# sheet1.net
KiCad netlist of a schematic drawn in Altium Designer
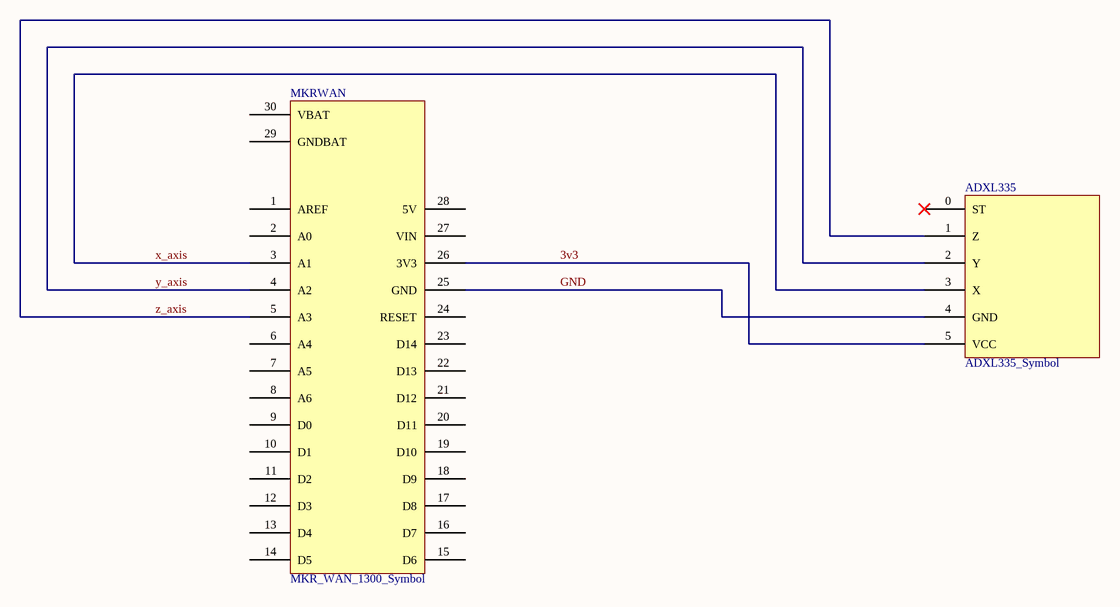
[diagram p0: sheet1.SchDoc]

(export (version "E")
  (design (tool "Eeschema 10.0.6"))
  (components
    (comp (ref "ADXL335")
      (value "ADXL335_Symbol")
      (footprint "ADXL335_HEADERS")
      (libsource (lib "Schlib1") (part "ADXL335_Symbol"))
    )
    (comp (ref "MKRWAN")
      (value "MKR_WAN_1300_Symbol")
      (footprint "MKR_WAN_1300_Headers")
      (libsource (lib "Schlib1") (part "MKR_WAN_1300_Symbol"))
    )
  )
  (nets
    (net (code "1") (name "/3v3") (class "Default")
      (node (ref "ADXL335") (pin "5") (pinfunction "VCC_5") (pintype "passive"))
      (node (ref "MKRWAN") (pin "26") (pinfunction "3V3_26") (pintype "passive"))
    )
    (net (code "2") (name "/GND") (class "Default")
      (node (ref "ADXL335") (pin "4") (pinfunction "GND_4") (pintype "passive"))
      (node (ref "MKRWAN") (pin "25") (pinfunction "GND_25") (pintype "passive"))
    )
    (net (code "3") (name "/x_axis") (class "Default")
      (node (ref "ADXL335") (pin "3") (pinfunction "X_3") (pintype "passive"))
      (node (ref "MKRWAN") (pin "3") (pinfunction "A1_3") (pintype "passive"))
    )
    (net (code "4") (name "/y_axis") (class "Default")
      (node (ref "ADXL335") (pin "2") (pinfunction "Y_2") (pintype "passive"))
      (node (ref "MKRWAN") (pin "4") (pinfunction "A2_4") (pintype "passive"))
    )
    (net (code "5") (name "/z_axis") (class "Default")
      (node (ref "ADXL335") (pin "1") (pinfunction "Z_1") (pintype "passive"))
      (node (ref "MKRWAN") (pin "5") (pinfunction "A3_5") (pintype "passive"))
    )
    (net (code "6") (name "unconnected-(ADXL335-ST-Pad0)") (class "Default")
      (node (ref "ADXL335") (pin "0") (pinfunction "ST_0") (pintype "passive+no_connect"))
    )
    (net (code "7") (name "unconnected-(MKRWAN-5V-Pad28)") (class "Default")
      (node (ref "MKRWAN") (pin "28") (pinfunction "5V_28") (pintype "passive"))
    )
    (net (code "8") (name "unconnected-(MKRWAN-A0-Pad2)") (class "Default")
      (node (ref "MKRWAN") (pin "2") (pinfunction "A0_2") (pintype "passive"))
    )
    (net (code "9") (name "unconnected-(MKRWAN-A4-Pad6)") (class "Default")
      (node (ref "MKRWAN") (pin "6") (pinfunction "A4_6") (pintype "passive"))
    )
    (net (code "10") (name "unconnected-(MKRWAN-A5-Pad7)") (class "Default")
      (node (ref "MKRWAN") (pin "7") (pinfunction "A5_7") (pintype "passive"))
    )
    (net (code "11") (name "unconnected-(MKRWAN-A6-Pad8)") (class "Default")
      (node (ref "MKRWAN") (pin "8") (pinfunction "A6_8") (pintype "passive"))
    )
    (net (code "12") (name "unconnected-(MKRWAN-AREF-Pad1)") (class "Default")
      (node (ref "MKRWAN") (pin "1") (pinfunction "AREF_1") (pintype "passive"))
    )
    (net (code "13") (name "unconnected-(MKRWAN-D0-Pad9)") (class "Default")
      (node (ref "MKRWAN") (pin "9") (pinfunction "D0_9") (pintype "passive"))
    )
    (net (code "14") (name "unconnected-(MKRWAN-D1-Pad10)") (class "Default")
      (node (ref "MKRWAN") (pin "10") (pinfunction "D1_10") (pintype "passive"))
    )
    (net (code "15") (name "unconnected-(MKRWAN-D2-Pad11)") (class "Default")
      (node (ref "MKRWAN") (pin "11") (pinfunction "D2_11") (pintype "passive"))
    )
    (net (code "16") (name "unconnected-(MKRWAN-D3-Pad12)") (class "Default")
      (node (ref "MKRWAN") (pin "12") (pinfunction "D3_12") (pintype "passive"))
    )
    (net (code "17") (name "unconnected-(MKRWAN-D4-Pad13)") (class "Default")
      (node (ref "MKRWAN") (pin "13") (pinfunction "D4_13") (pintype "passive"))
    )
    (net (code "18") (name "unconnected-(MKRWAN-D5-Pad14)") (class "Default")
      (node (ref "MKRWAN") (pin "14") (pinfunction "D5_14") (pintype "passive"))
    )
    (net (code "19") (name "unconnected-(MKRWAN-D6-Pad15)") (class "Default")
      (node (ref "MKRWAN") (pin "15") (pinfunction "D6_15") (pintype "passive"))
    )
    (net (code "20") (name "unconnected-(MKRWAN-D7-Pad16)") (class "Default")
      (node (ref "MKRWAN") (pin "16") (pinfunction "D7_16") (pintype "passive"))
    )
    (net (code "21") (name "unconnected-(MKRWAN-D8-Pad17)") (class "Default")
      (node (ref "MKRWAN") (pin "17") (pinfunction "D8_17") (pintype "passive"))
    )
    (net (code "22") (name "unconnected-(MKRWAN-D9-Pad18)") (class "Default")
      (node (ref "MKRWAN") (pin "18") (pinfunction "D9_18") (pintype "passive"))
    )
    (net (code "23") (name "unconnected-(MKRWAN-D10-Pad19)") (class "Default")
      (node (ref "MKRWAN") (pin "19") (pinfunction "D10_19") (pintype "passive"))
    )
    (net (code "24") (name "unconnected-(MKRWAN-D11-Pad20)") (class "Default")
      (node (ref "MKRWAN") (pin "20") (pinfunction "D11_20") (pintype "passive"))
    )
    (net (code "25") (name "unconnected-(MKRWAN-D12-Pad21)") (class "Default")
      (node (ref "MKRWAN") (pin "21") (pinfunction "D12_21") (pintype "passive"))
    )
    (net (code "26") (name "unconnected-(MKRWAN-D13-Pad22)") (class "Default")
      (node (ref "MKRWAN") (pin "22") (pinfunction "D13_22") (pintype "passive"))
    )
    (net (code "27") (name "unconnected-(MKRWAN-D14-Pad23)") (class "Default")
      (node (ref "MKRWAN") (pin "23") (pinfunction "D14_23") (pintype "passive"))
    )
    (net (code "28") (name "unconnected-(MKRWAN-GNDBAT-Pad29)") (class "Default")
      (node (ref "MKRWAN") (pin "29") (pinfunction "GNDBAT_29") (pintype "passive"))
    )
    (net (code "29") (name "unconnected-(MKRWAN-RESET-Pad24)") (class "Default")
      (node (ref "MKRWAN") (pin "24") (pinfunction "RESET_24") (pintype "passive"))
    )
    (net (code "30") (name "unconnected-(MKRWAN-VBAT-Pad30)") (class "Default")
      (node (ref "MKRWAN") (pin "30") (pinfunction "VBAT_30") (pintype "passive"))
    )
    (net (code "31") (name "unconnected-(MKRWAN-VIN-Pad27)") (class "Default")
      (node (ref "MKRWAN") (pin "27") (pinfunction "VIN_27") (pintype "passive"))
    )
  )
)
